# ECU_Sheet2.net
KiCad netlist of a schematic drawn in Altium Designer
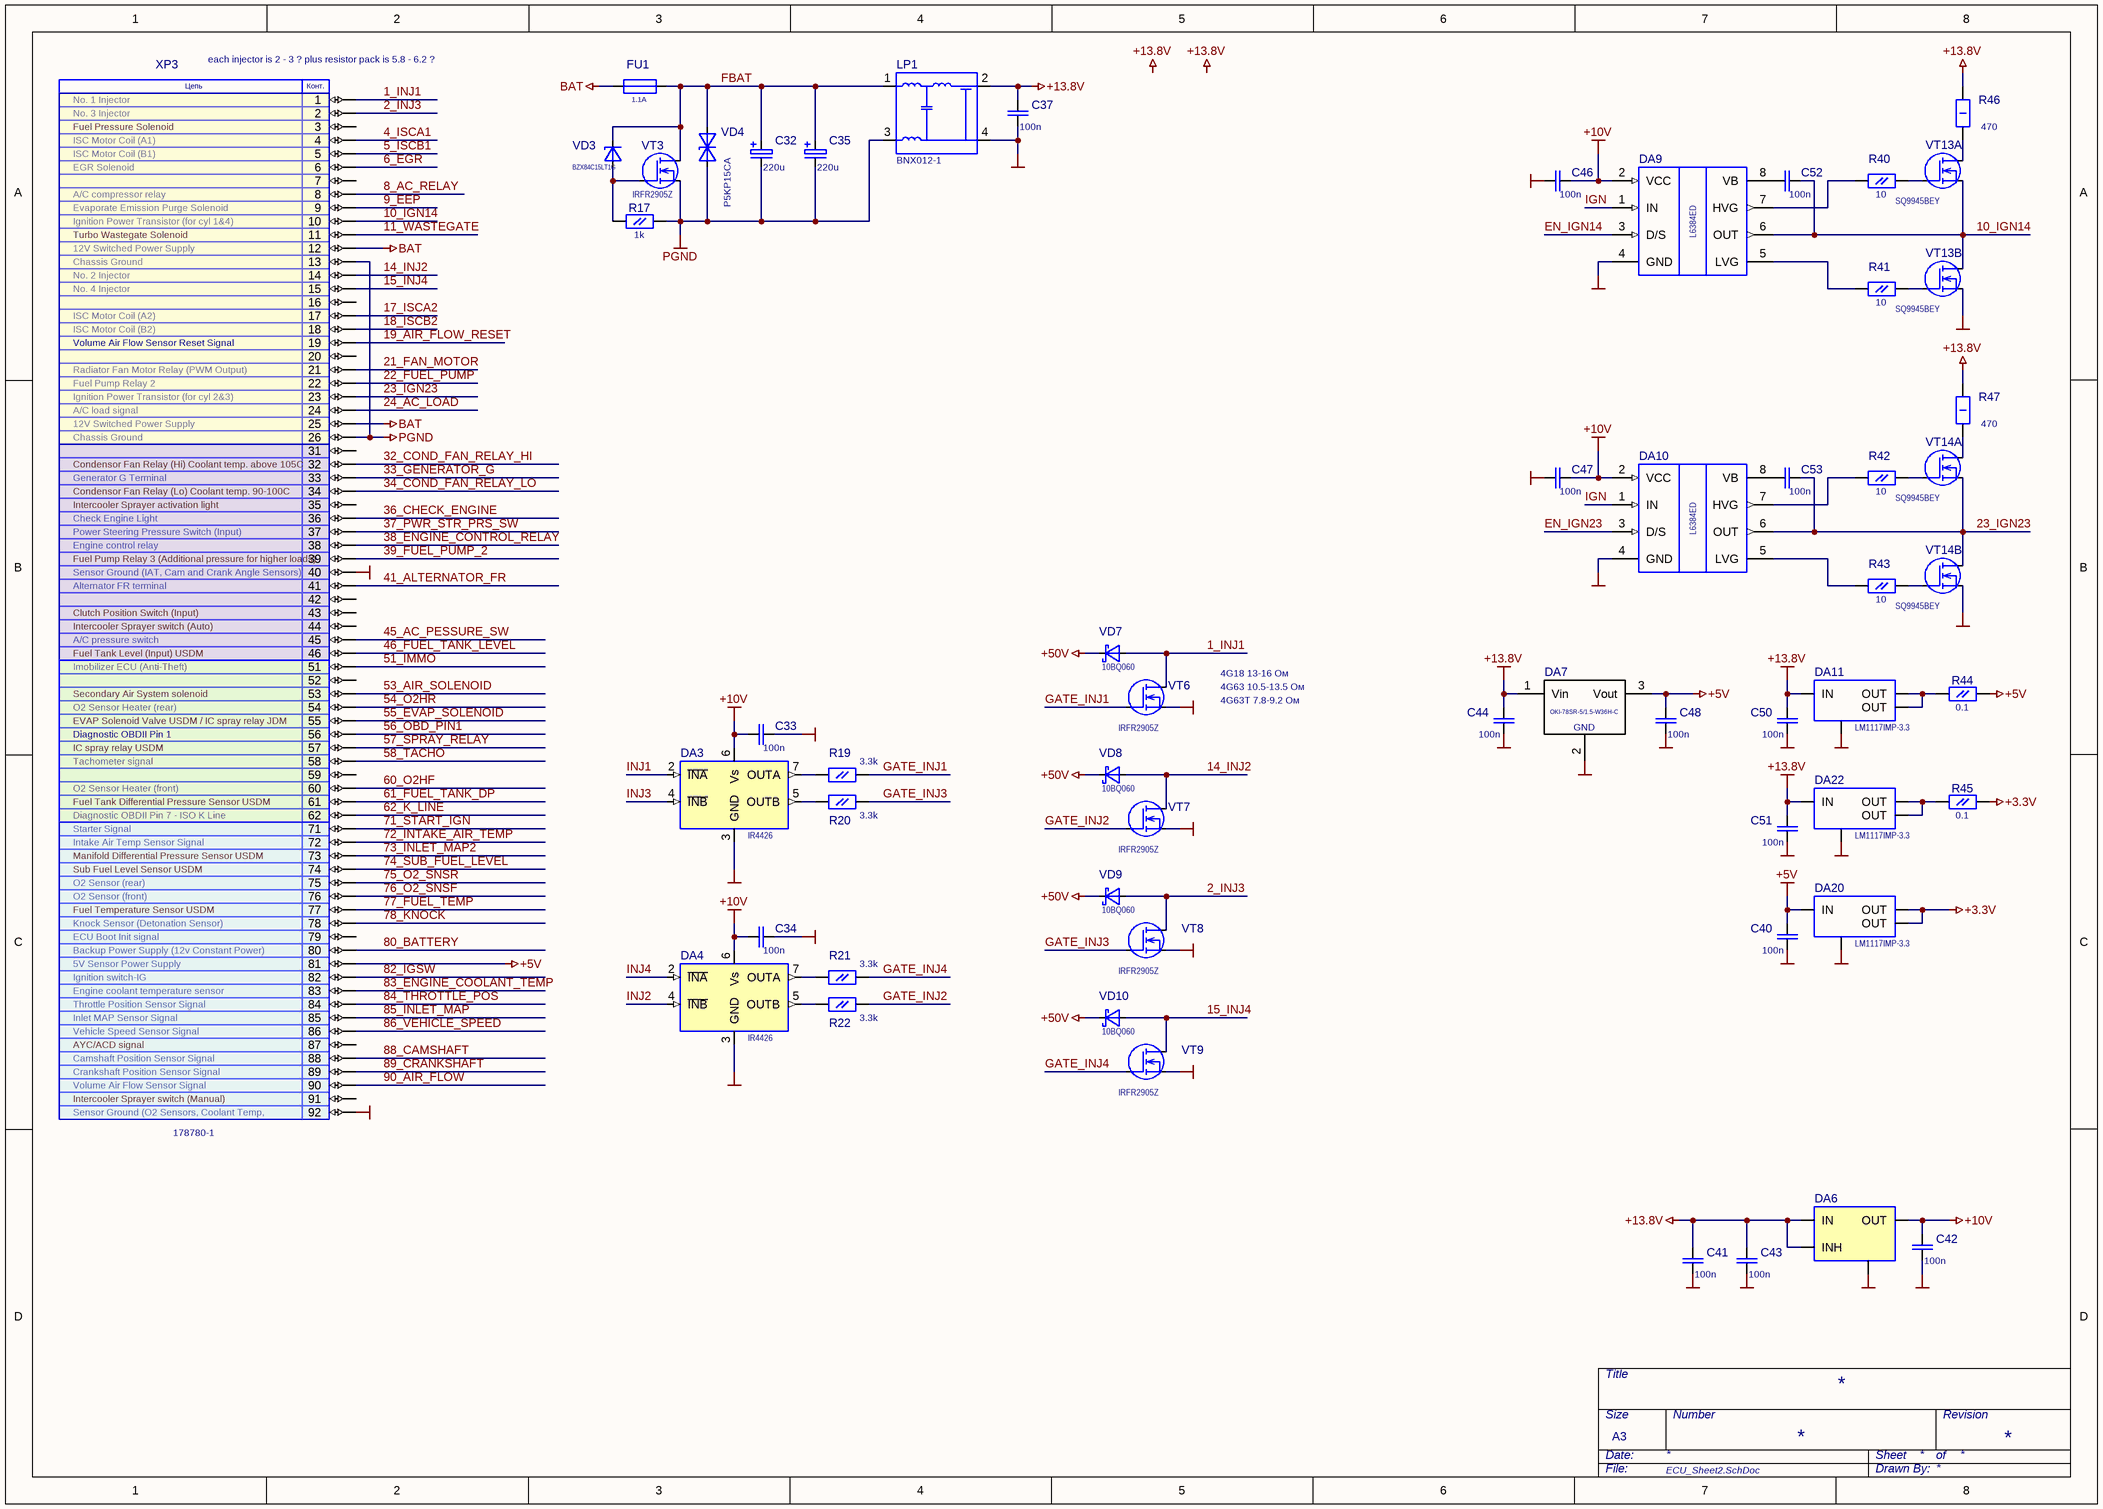
[diagram p0: ECU_Sheet2.SchDoc]

(export (version "E")
  (design (tool "Eeschema 10.0.6"))
  (components
    (comp (ref "C32")
      (value "220u")
      (footprint "C_D_POL")
      (description "220 mkF  25 v (корпус Е (4,4х7мм))  20% smd   Танталовый    ЧИП    227M025V")
      (fields (field (name "Comment") "CTANT"))
      (libsource (lib "L1") (part "CTANT"))
    )
    (comp (ref "C33")
      (value "100n")
      (footprint "C0805L")
      (description "C0603")
      (fields (field (name "Comment") "CSMD"))
      (libsource (lib "L1") (part "CSMD"))
    )
    (comp (ref "C34")
      (value "100n")
      (footprint "C0805L")
      (description "C0603")
      (fields (field (name "Comment") "CSMD"))
      (libsource (lib "L1") (part "CSMD"))
    )
    (comp (ref "C35")
      (value "220u")
      (footprint "C_D_POL")
      (description "220 mkF  25 v (корпус Е (4,4х7мм))  20% smd   Танталовый    ЧИП    227M025V")
      (fields (field (name "Comment") "CTANT"))
      (libsource (lib "L1") (part "CTANT"))
    )
    (comp (ref "C37")
      (value "100n")
      (footprint "C0805L")
      (description "C0603")
      (fields (field (name "Comment") "0.1мкФ-25В-X8R-10%"))
      (libsource (lib "L1") (part "CSMD"))
    )
    (comp (ref "C40")
      (value "100n")
      (footprint "C0805L")
      (description "C0603")
      (fields (field (name "Comment") "CSMD"))
      (libsource (lib "L1") (part "CSMD"))
    )
    (comp (ref "C41")
      (value "100n")
      (footprint "C0805L")
      (description "C0603")
      (fields (field (name "Comment") "0.1мкФ-25В-X8R-10%"))
      (libsource (lib "L1") (part "CSMD"))
    )
    (comp (ref "C42")
      (value "100n")
      (footprint "C0805L")
      (description "C0603")
      (fields (field (name "Comment") "0.1мкФ-25В-X8R-10%"))
      (libsource (lib "L1") (part "CSMD"))
    )
    (comp (ref "C43")
      (value "100n")
      (footprint "C0805L")
      (description "C0603")
      (fields (field (name "Comment") "0.1мкФ-25В-X8R-10%"))
      (libsource (lib "L1") (part "CSMD"))
    )
    (comp (ref "C44")
      (value "100n")
      (footprint "C0805L")
      (description "C0603")
      (fields (field (name "Comment") "CSMD"))
      (libsource (lib "L1") (part "CSMD"))
    )
    (comp (ref "C46")
      (value "100n")
      (footprint "C0805L")
      (description "C0603")
      (fields (field (name "Comment") "CSMD"))
      (libsource (lib "L1") (part "CSMD"))
    )
    (comp (ref "C47")
      (value "100n")
      (footprint "C0805L")
      (description "C0603")
      (fields (field (name "Comment") "CSMD"))
      (libsource (lib "L1") (part "CSMD"))
    )
    (comp (ref "C48")
      (value "100n")
      (footprint "C0805L")
      (description "C0603")
      (fields (field (name "Comment") "CSMD"))
      (libsource (lib "L1") (part "CSMD"))
    )
    (comp (ref "C50")
      (value "100n")
      (footprint "C0805L")
      (description "C0603")
      (fields (field (name "Comment") "CSMD"))
      (libsource (lib "L1") (part "CSMD"))
    )
    (comp (ref "C51")
      (value "100n")
      (footprint "C0805L")
      (description "C0603")
      (fields (field (name "Comment") "CSMD"))
      (libsource (lib "L1") (part "CSMD"))
    )
    (comp (ref "C52")
      (value "100n")
      (footprint "C0805L")
      (description "C0603")
      (fields (field (name "Comment") "CSMD"))
      (libsource (lib "L1") (part "CSMD"))
    )
    (comp (ref "C53")
      (value "100n")
      (footprint "C0805L")
      (description "C0603")
      (fields (field (name "Comment") "CSMD"))
      (libsource (lib "L1") (part "CSMD"))
    )
    (comp (ref "DA3") (value "IR4426") (footprint "SOIC8 JEDEC") (libsource (lib "SCH") (part "IR4426")))
    (comp (ref "DA4") (value "IR4426") (footprint "SOIC8 JEDEC") (libsource (lib "SCH") (part "IR4426")))
    (comp (ref "DA6")
      (value "TLE4266GS V10")
      (footprint "SOT-223")
      (description "TLE4266G")
      (libsource (lib "L1") (part "TLE4266G"))
    )
    (comp (ref "DA7")
      (value "OKI-78SR-5/1.5-W36H-C")
      (footprint "OKI-78SR-H")
      (description "Fixed Output 1.5 Amp SIP DC/DC Converter")
      (libsource (lib "L1") (part "OKI-78SR"))
    )
    (comp (ref "DA9") (value "L6384ED") (footprint "SOIC8 JEDEC") (libsource (lib "ECULIB") (part "L6384ED")))
    (comp (ref "DA10")
      (value "L6384ED")
      (footprint "SOIC8 JEDEC")
      (libsource (lib "ECULIB") (part "L6384ED"))
    )
    (comp (ref "DA11")
      (value "LM1117IMP-3.3")
      (footprint "SOT-223")
      (libsource (lib "RL1") (part "LM1117IMP-3.3"))
    )
    (comp (ref "DA20")
      (value "LM1117IMP-3.3")
      (footprint "SOT-223")
      (libsource (lib "RL1") (part "LM1117IMP-3.3"))
    )
    (comp (ref "DA22")
      (value "LM1117IMP-3.3")
      (footprint "SOT-223")
      (libsource (lib "RL1") (part "LM1117IMP-3.3"))
    )
    (comp (ref "FU1")
      (value "1.1A")
      (footprint "FUSE1206")
      (description "MF-NSMF110")
      (libsource (lib "RL1") (part "MF-NSMF012"))
    )
    (comp (ref "LP1") (value "BNX012-1") (footprint "BNX012-01") (libsource (lib "RL1") (part "BNX012-1")))
    (comp (ref "R17")
      (value "1k")
      (footprint "R0805L")
      (description "R0805")
      (fields (field (name "Comment") "1к-5%"))
      (libsource (lib "L1") (part "RSMD"))
    )
    (comp (ref "R19")
      (value "3.3k")
      (footprint "R0603L")
      (description "R0805")
      (fields (field (name "Comment") "RSMD"))
      (libsource (lib "L1") (part "RSMD"))
    )
    (comp (ref "R20")
      (value "3.3k")
      (footprint "R0603L")
      (description "R0805")
      (fields (field (name "Comment") "RSMD"))
      (libsource (lib "L1") (part "RSMD"))
    )
    (comp (ref "R21")
      (value "3.3k")
      (footprint "R0603L")
      (description "R0805")
      (fields (field (name "Comment") "RSMD"))
      (libsource (lib "L1") (part "RSMD"))
    )
    (comp (ref "R22")
      (value "3.3k")
      (footprint "R0603L")
      (description "R0805")
      (fields (field (name "Comment") "RSMD"))
      (libsource (lib "L1") (part "RSMD"))
    )
    (comp (ref "R40")
      (value "10")
      (footprint "R0603L")
      (description "R0805")
      (fields (field (name "Comment") "RSMD"))
      (libsource (lib "L1") (part "RSMD"))
    )
    (comp (ref "R41")
      (value "10")
      (footprint "R0603L")
      (description "R0805")
      (fields (field (name "Comment") "RSMD"))
      (libsource (lib "L1") (part "RSMD"))
    )
    (comp (ref "R42")
      (value "10")
      (footprint "R0603L")
      (description "R0805")
      (fields (field (name "Comment") "RSMD"))
      (libsource (lib "L1") (part "RSMD"))
    )
    (comp (ref "R43")
      (value "10")
      (footprint "R0603L")
      (description "R0805")
      (fields (field (name "Comment") "RSMD"))
      (libsource (lib "L1") (part "RSMD"))
    )
    (comp (ref "R44")
      (value "0.1")
      (footprint "R0805L")
      (description "R0805")
      (fields (field (name "Comment") "1к-5%"))
      (libsource (lib "L1") (part "RSMD"))
    )
    (comp (ref "R45")
      (value "0.1")
      (footprint "R0805L")
      (description "R0805")
      (fields (field (name "Comment") "1к-5%"))
      (libsource (lib "L1") (part "RSMD"))
    )
    (comp (ref "R46")
      (value "470")
      (footprint "R2512")
      (description "R2512")
      (libsource (lib "RL1") (part "R2512"))
    )
    (comp (ref "R47")
      (value "470")
      (footprint "R2512")
      (description "R2512")
      (libsource (lib "RL1") (part "R2512"))
    )
    (comp (ref "VD3") (value "BZX84C15LT1G") (footprint "SOT-23") (libsource (lib "RL1") (part "BZX84C36")))
    (comp (ref "VD4") (value "P5KP15CA") (footprint "P600") (libsource (lib "L1") (part "P5KP15CA")))
    (comp (ref "VD7")
      (value "10BQ060")
      (footprint "RL1:DO-214AA SMB")
      (libsource (lib "RL1") (part "10BQ060"))
    )
    (comp (ref "VD8")
      (value "10BQ060")
      (footprint "RL1:DO-214AA SMB")
      (libsource (lib "RL1") (part "10BQ060"))
    )
    (comp (ref "VD9")
      (value "10BQ060")
      (footprint "RL1:DO-214AA SMB")
      (libsource (lib "RL1") (part "10BQ060"))
    )
    (comp (ref "VD10")
      (value "10BQ060")
      (footprint "RL1:DO-214AA SMB")
      (libsource (lib "RL1") (part "10BQ060"))
    )
    (comp (ref "VT3")
      (value "IRFR2905Z")
      (footprint "D-PAK (TO-252)")
      (description "MOSFET 55V , 42A , 0.011 Om")
      (libsource (lib "RL1") (part "SPD02N80C3"))
    )
    (comp (ref "VT6")
      (value "IRFR2905Z")
      (footprint "D-PAK (TO-252)")
      (description "MOSFET 55V , 42A , 0.011 Om")
      (libsource (lib "RL1") (part "SPD02N80C3"))
    )
    (comp (ref "VT7")
      (value "IRFR2905Z")
      (footprint "D-PAK (TO-252)")
      (description "MOSFET 55V , 42A , 0.011 Om")
      (libsource (lib "RL1") (part "SPD02N80C3"))
    )
    (comp (ref "VT8")
      (value "IRFR2905Z")
      (footprint "D-PAK (TO-252)")
      (description "MOSFET 55V , 42A , 0.011 Om")
      (libsource (lib "RL1") (part "SPD02N80C3"))
    )
    (comp (ref "VT9")
      (value "IRFR2905Z")
      (footprint "D-PAK (TO-252)")
      (description "MOSFET 55V , 42A , 0.011 Om")
      (libsource (lib "RL1") (part "SPD02N80C3"))
    )
    (comp (ref "VT13")
      (value "SQ9945BEY")
      (footprint "SOIC8 DBL FET")
      (libsource (lib "L1") (part "SQ9945BEY"))
    )
    (comp (ref "VT14")
      (value "SQ9945BEY")
      (footprint "SOIC8 DBL FET")
      (libsource (lib "L1") (part "SQ9945BEY"))
    )
    (comp (ref "XP3")
      (value "178780-1")
      (footprint "MITSUBISHI_ECU_CON")
      (description "TE 178780-1")
      (libsource (lib "ECULIB") (part "MITSUBISHI_ECU_CON"))
    )
  )
  (nets
    (net (code "1") (name "+3.3V") (class "Default")
      (node (ref "DA20") (pin "2") (pinfunction "OUT_2") (pintype "passive"))
      (node (ref "DA20") (pin "4") (pinfunction "OUT_4") (pintype "passive"))
      (node (ref "R45") (pin "1") (pinfunction "Pin1_1") (pintype "passive"))
    )
    (net (code "2") (name "+5V") (class "Default")
      (node (ref "C40") (pin "1") (pintype "passive"))
      (node (ref "C48") (pin "1") (pintype "passive"))
      (node (ref "DA20") (pin "3") (pinfunction "IN_3") (pintype "passive"))
      (node (ref "DA7") (pin "3") (pinfunction "Vout_3") (pintype "passive"))
      (node (ref "R44") (pin "1") (pinfunction "Pin1_1") (pintype "passive"))
      (node (ref "XP3") (pin "81") (pinfunction "81_81") (pintype "bidirectional"))
    )
    (net (code "3") (name "+10V") (class "Default")
      (node (ref "C33") (pin "2") (pintype "passive"))
      (node (ref "C34") (pin "2") (pintype "passive"))
      (node (ref "C42") (pin "1") (pintype "passive"))
      (node (ref "C46") (pin "1") (pintype "passive"))
      (node (ref "C47") (pin "1") (pintype "passive"))
      (node (ref "DA10") (pin "2") (pinfunction "VCC_2") (pintype "input"))
      (node (ref "DA3") (pin "6") (pinfunction "Vs_6") (pintype "power_in"))
      (node (ref "DA4") (pin "6") (pinfunction "Vs_6") (pintype "power_in"))
      (node (ref "DA6") (pin "3") (pinfunction "OUT_3") (pintype "passive"))
      (node (ref "DA9") (pin "2") (pinfunction "VCC_2") (pintype "input"))
    )
    (net (code "4") (name "+13.8V") (class "Default")
      (node (ref "C37") (pin "1") (pintype "passive"))
      (node (ref "C41") (pin "1") (pintype "passive"))
      (node (ref "C43") (pin "1") (pintype "passive"))
      (node (ref "C44") (pin "1") (pintype "passive"))
      (node (ref "C50") (pin "1") (pintype "passive"))
      (node (ref "C51") (pin "1") (pintype "passive"))
      (node (ref "DA11") (pin "3") (pinfunction "IN_3") (pintype "passive"))
      (node (ref "DA22") (pin "3") (pinfunction "IN_3") (pintype "passive"))
      (node (ref "DA6") (pin "1") (pinfunction "IN_1") (pintype "passive"))
      (node (ref "DA6") (pin "2") (pinfunction "INH_2") (pintype "passive"))
      (node (ref "DA7") (pin "1") (pinfunction "Vin_1") (pintype "passive"))
      (node (ref "LP1") (pin "2") (pinfunction "CB_2") (pintype "passive"))
      (node (ref "R46") (pin "2") (pinfunction "Pin2_2") (pintype "passive"))
      (node (ref "R47") (pin "2") (pinfunction "Pin2_2") (pintype "passive"))
    )
    (net (code "5") (name "+50V") (class "Default")
      (node (ref "VD10") (pin "2") (pintype "passive"))
      (node (ref "VD7") (pin "2") (pintype "passive"))
      (node (ref "VD8") (pin "2") (pintype "passive"))
      (node (ref "VD9") (pin "2") (pintype "passive"))
    )
    (net (code "6") (name "/1_INJ1") (class "Default")
      (node (ref "VD7") (pin "1") (pintype "passive"))
      (node (ref "VT6") (pin "3") (pinfunction "D_3") (pintype "passive"))
      (node (ref "XP3") (pin "1") (pinfunction "1_1") (pintype "bidirectional"))
    )
    (net (code "7") (name "/2_INJ3") (class "Default")
      (node (ref "VD9") (pin "1") (pintype "passive"))
      (node (ref "VT8") (pin "3") (pinfunction "D_3") (pintype "passive"))
      (node (ref "XP3") (pin "2") (pinfunction "2_2") (pintype "bidirectional"))
    )
    (net (code "8") (name "/4_ISCA1") (class "Default")
      (node (ref "XP3") (pin "4") (pinfunction "4_4") (pintype "bidirectional"))
    )
    (net (code "9") (name "/5_ISCB1") (class "Default")
      (node (ref "XP3") (pin "5") (pinfunction "5_5") (pintype "bidirectional"))
    )
    (net (code "10") (name "/6_EGR") (class "Default")
      (node (ref "XP3") (pin "6") (pinfunction "6_6") (pintype "bidirectional"))
    )
    (net (code "11") (name "/8_AC_RELAY") (class "Default")
      (node (ref "XP3") (pin "8") (pinfunction "8_8") (pintype "bidirectional"))
    )
    (net (code "12") (name "/9_EEP") (class "Default")
      (node (ref "XP3") (pin "9") (pinfunction "9_9") (pintype "bidirectional"))
    )
    (net (code "13") (name "/10_IGN14") (class "Default")
      (node (ref "C52") (pin "1") (pintype "passive"))
      (node (ref "DA9") (pin "6") (pinfunction "OUT_6") (pintype "output"))
      (node (ref "VT13") (pin "1") (pintype "passive"))
      (node (ref "VT13") (pin "5") (pintype "passive"))
      (node (ref "XP3") (pin "10") (pinfunction "10_10") (pintype "bidirectional"))
    )
    (net (code "14") (name "/11_WASTEGATE") (class "Default")
      (node (ref "XP3") (pin "11") (pinfunction "11_11") (pintype "bidirectional"))
    )
    (net (code "15") (name "/14_INJ2") (class "Default")
      (node (ref "VD8") (pin "1") (pintype "passive"))
      (node (ref "VT7") (pin "3") (pinfunction "D_3") (pintype "passive"))
      (node (ref "XP3") (pin "14") (pinfunction "14_14") (pintype "bidirectional"))
    )
    (net (code "16") (name "/15_INJ4") (class "Default")
      (node (ref "VD10") (pin "1") (pintype "passive"))
      (node (ref "VT9") (pin "3") (pinfunction "D_3") (pintype "passive"))
      (node (ref "XP3") (pin "15") (pinfunction "15_15") (pintype "bidirectional"))
    )
    (net (code "17") (name "/17_ISCA2") (class "Default")
      (node (ref "XP3") (pin "17") (pinfunction "17_17") (pintype "bidirectional"))
    )
    (net (code "18") (name "/18_ISCB2") (class "Default")
      (node (ref "XP3") (pin "18") (pinfunction "18_18") (pintype "bidirectional"))
    )
    (net (code "19") (name "/19_AIR_FLOW_RESET") (class "Default")
      (node (ref "XP3") (pin "19") (pinfunction "19_19") (pintype "bidirectional"))
    )
    (net (code "20") (name "/21_FAN_MOTOR") (class "Default")
      (node (ref "XP3") (pin "21") (pinfunction "21_21") (pintype "bidirectional"))
    )
    (net (code "21") (name "/22_FUEL_PUMP") (class "Default")
      (node (ref "XP3") (pin "22") (pinfunction "22_22") (pintype "bidirectional"))
    )
    (net (code "22") (name "/23_IGN23") (class "Default")
      (node (ref "C53") (pin "1") (pintype "passive"))
      (node (ref "DA10") (pin "6") (pinfunction "OUT_6") (pintype "output"))
      (node (ref "VT14") (pin "1") (pintype "passive"))
      (node (ref "VT14") (pin "5") (pintype "passive"))
      (node (ref "XP3") (pin "23") (pinfunction "23_23") (pintype "bidirectional"))
    )
    (net (code "23") (name "/24_AC_LOAD") (class "Default")
      (node (ref "XP3") (pin "24") (pinfunction "24_24") (pintype "bidirectional"))
    )
    (net (code "24") (name "/32_COND_FAN_RELAY_HI") (class "Default")
      (node (ref "XP3") (pin "32") (pinfunction "32_32") (pintype "bidirectional"))
    )
    (net (code "25") (name "/33_GENERATOR_G") (class "Default")
      (node (ref "XP3") (pin "33") (pinfunction "33_33") (pintype "bidirectional"))
    )
    (net (code "26") (name "/34_COND_FAN_RELAY_LO") (class "Default")
      (node (ref "XP3") (pin "34") (pinfunction "34_34") (pintype "bidirectional"))
    )
    (net (code "27") (name "/36_CHECK_ENGINE") (class "Default")
      (node (ref "XP3") (pin "36") (pinfunction "36_36") (pintype "bidirectional"))
    )
    (net (code "28") (name "/37_PWR_STR_PRS_SW") (class "Default")
      (node (ref "XP3") (pin "37") (pinfunction "37_37") (pintype "bidirectional"))
    )
    (net (code "29") (name "/38_ENGINE_CONTROL_RELAY") (class "Default")
      (node (ref "XP3") (pin "38") (pinfunction "38_38") (pintype "bidirectional"))
    )
    (net (code "30") (name "/39_FUEL_PUMP_2") (class "Default")
      (node (ref "XP3") (pin "39") (pinfunction "39_39") (pintype "bidirectional"))
    )
    (net (code "31") (name "/41_ALTERNATOR_FR") (class "Default")
      (node (ref "XP3") (pin "41") (pinfunction "41_41") (pintype "bidirectional"))
    )
    (net (code "32") (name "/45_AC_PESSURE_SW") (class "Default")
      (node (ref "XP3") (pin "45") (pinfunction "45_45") (pintype "bidirectional"))
    )
    (net (code "33") (name "/46_FUEL_TANK_LEVEL") (class "Default")
      (node (ref "XP3") (pin "46") (pinfunction "46_46") (pintype "bidirectional"))
    )
    (net (code "34") (name "/51_IMMO") (class "Default")
      (node (ref "XP3") (pin "51") (pinfunction "51_51") (pintype "bidirectional"))
    )
    (net (code "35") (name "/53_AIR_SOLENOID") (class "Default")
      (node (ref "XP3") (pin "53") (pinfunction "53_53") (pintype "bidirectional"))
    )
    (net (code "36") (name "/54_O2HR") (class "Default")
      (node (ref "XP3") (pin "54") (pinfunction "54_54") (pintype "bidirectional"))
    )
    (net (code "37") (name "/55_EVAP_SOLENOID") (class "Default")
      (node (ref "XP3") (pin "55") (pinfunction "55_55") (pintype "bidirectional"))
    )
    (net (code "38") (name "/56_OBD_PIN1") (class "Default")
      (node (ref "XP3") (pin "56") (pinfunction "56_56") (pintype "bidirectional"))
    )
    (net (code "39") (name "/57_SPRAY_RELAY") (class "Default")
      (node (ref "XP3") (pin "57") (pinfunction "57_57") (pintype "bidirectional"))
    )
    (net (code "40") (name "/58_TACHO") (class "Default")
      (node (ref "XP3") (pin "58") (pinfunction "58_58") (pintype "bidirectional"))
    )
    (net (code "41") (name "/60_O2HF") (class "Default")
      (node (ref "XP3") (pin "60") (pinfunction "60_60") (pintype "bidirectional"))
    )
    (net (code "42") (name "/61_FUEL_TANK_DP") (class "Default")
      (node (ref "XP3") (pin "61") (pinfunction "61_61") (pintype "bidirectional"))
    )
    (net (code "43") (name "/62_K_LINE") (class "Default")
      (node (ref "XP3") (pin "62") (pinfunction "62_62") (pintype "bidirectional"))
    )
    (net (code "44") (name "/71_START_IGN") (class "Default")
      (node (ref "XP3") (pin "71") (pinfunction "71_71") (pintype "bidirectional"))
    )
    (net (code "45") (name "/72_INTAKE_AIR_TEMP") (class "Default")
      (node (ref "XP3") (pin "72") (pinfunction "72_72") (pintype "bidirectional"))
    )
    (net (code "46") (name "/73_INLET_MAP2") (class "Default")
      (node (ref "XP3") (pin "73") (pinfunction "73_73") (pintype "bidirectional"))
    )
    (net (code "47") (name "/74_SUB_FUEL_LEVEL") (class "Default")
      (node (ref "XP3") (pin "74") (pinfunction "74_74") (pintype "bidirectional"))
    )
    (net (code "48") (name "/75_O2_SNSR") (class "Default")
      (node (ref "XP3") (pin "75") (pinfunction "75_75") (pintype "bidirectional"))
    )
    (net (code "49") (name "/76_O2_SNSF") (class "Default")
      (node (ref "XP3") (pin "76") (pinfunction "76_76") (pintype "bidirectional"))
    )
    (net (code "50") (name "/77_FUEL_TEMP") (class "Default")
      (node (ref "XP3") (pin "77") (pinfunction "77_77") (pintype "bidirectional"))
    )
    (net (code "51") (name "/78_KNOCK") (class "Default")
      (node (ref "XP3") (pin "78") (pinfunction "78_78") (pintype "bidirectional"))
    )
    (net (code "52") (name "/80_BATTERY") (class "Default")
      (node (ref "XP3") (pin "80") (pinfunction "80_80") (pintype "bidirectional"))
    )
    (net (code "53") (name "/82_IGSW") (class "Default")
      (node (ref "XP3") (pin "82") (pinfunction "82_82") (pintype "bidirectional"))
    )
    (net (code "54") (name "/83_ENGINE_COOLANT_TEMP") (class "Default")
      (node (ref "XP3") (pin "83") (pinfunction "83_83") (pintype "bidirectional"))
    )
    (net (code "55") (name "/84_THROTTLE_POS") (class "Default")
      (node (ref "XP3") (pin "84") (pinfunction "84_84") (pintype "bidirectional"))
    )
    (net (code "56") (name "/85_INLET_MAP") (class "Default")
      (node (ref "XP3") (pin "85") (pinfunction "85_85") (pintype "bidirectional"))
    )
    (net (code "57") (name "/86_VEHICLE_SPEED") (class "Default")
      (node (ref "XP3") (pin "86") (pinfunction "86_86") (pintype "bidirectional"))
    )
    (net (code "58") (name "/88_CAMSHAFT") (class "Default")
      (node (ref "XP3") (pin "88") (pinfunction "88_88") (pintype "bidirectional"))
    )
    (net (code "59") (name "/89_CRANKSHAFT") (class "Default")
      (node (ref "XP3") (pin "89") (pinfunction "89_89") (pintype "bidirectional"))
    )
    (net (code "60") (name "/90_AIR_FLOW") (class "Default")
      (node (ref "XP3") (pin "90") (pinfunction "90_90") (pintype "bidirectional"))
    )
    (net (code "61") (name "/EN_IGN14") (class "Default")
      (node (ref "DA9") (pin "3") (pinfunction "D/S_3") (pintype "input"))
    )
    (net (code "62") (name "/EN_IGN23") (class "Default")
      (node (ref "DA10") (pin "3") (pinfunction "D/S_3") (pintype "input"))
    )
    (net (code "63") (name "/FBAT") (class "Default")
      (node (ref "C32") (pin "P") (pintype "passive"))
      (node (ref "C35") (pin "P") (pintype "passive"))
      (node (ref "FU1") (pin "2") (pinfunction "2_2") (pintype "passive"))
      (node (ref "LP1") (pin "1") (pinfunction "B_1") (pintype "passive"))
      (node (ref "VD3") (pin "3") (pintype "passive"))
      (node (ref "VD4") (pin "2") (pintype "passive"))
      (node (ref "VT3") (pin "3") (pinfunction "D_3") (pintype "passive"))
    )
    (net (code "64") (name "/GATE_INJ1") (class "Default")
      (node (ref "R19") (pin "2") (pinfunction "Pin2_2") (pintype "passive"))
      (node (ref "VT6") (pin "1") (pinfunction "G_1") (pintype "passive"))
    )
    (net (code "65") (name "/GATE_INJ2") (class "Default")
      (node (ref "R22") (pin "2") (pinfunction "Pin2_2") (pintype "passive"))
      (node (ref "VT7") (pin "1") (pinfunction "G_1") (pintype "passive"))
    )
    (net (code "66") (name "/GATE_INJ3") (class "Default")
      (node (ref "R20") (pin "2") (pinfunction "Pin2_2") (pintype "passive"))
      (node (ref "VT8") (pin "1") (pinfunction "G_1") (pintype "passive"))
    )
    (net (code "67") (name "/GATE_INJ4") (class "Default")
      (node (ref "R21") (pin "2") (pinfunction "Pin2_2") (pintype "passive"))
      (node (ref "VT9") (pin "1") (pinfunction "G_1") (pintype "passive"))
    )
    (net (code "68") (name "/IGN") (class "Default")
      (node (ref "DA10") (pin "1") (pinfunction "IN_1") (pintype "input"))
      (node (ref "DA9") (pin "1") (pinfunction "IN_1") (pintype "input"))
    )
    (net (code "69") (name "/INJ1") (class "Default")
      (node (ref "DA3") (pin "2") (pinfunction "~{INA}_2") (pintype "input"))
    )
    (net (code "70") (name "/INJ2") (class "Default")
      (node (ref "DA4") (pin "4") (pinfunction "~{INB}_4") (pintype "input"))
    )
    (net (code "71") (name "/INJ3") (class "Default")
      (node (ref "DA3") (pin "4") (pinfunction "~{INB}_4") (pintype "input"))
    )
    (net (code "72") (name "/INJ4") (class "Default")
      (node (ref "DA4") (pin "2") (pinfunction "~{INA}_2") (pintype "input"))
    )
    (net (code "73") (name "BAT") (class "Default")
      (node (ref "FU1") (pin "1") (pinfunction "1_1") (pintype "passive"))
      (node (ref "XP3") (pin "12") (pinfunction "12_12") (pintype "bidirectional"))
      (node (ref "XP3") (pin "25") (pinfunction "25_25") (pintype "bidirectional"))
    )
    (net (code "74") (name "GND") (class "Default")
      (node (ref "C33") (pin "1") (pintype "passive"))
      (node (ref "C34") (pin "1") (pintype "passive"))
      (node (ref "C37") (pin "2") (pintype "passive"))
      (node (ref "C40") (pin "2") (pintype "passive"))
      (node (ref "C41") (pin "2") (pintype "passive"))
      (node (ref "C42") (pin "2") (pintype "passive"))
      (node (ref "C43") (pin "2") (pintype "passive"))
      (node (ref "C44") (pin "2") (pintype "passive"))
      (node (ref "C46") (pin "2") (pintype "passive"))
      (node (ref "C47") (pin "2") (pintype "passive"))
      (node (ref "C48") (pin "2") (pintype "passive"))
      (node (ref "C50") (pin "2") (pintype "passive"))
      (node (ref "C51") (pin "2") (pintype "passive"))
      (node (ref "DA10") (pin "4") (pinfunction "GND_4") (pintype "power_in"))
      (node (ref "DA11") (pin "1") (pinfunction "G_1") (pintype "passive"))
      (node (ref "DA20") (pin "1") (pinfunction "G_1") (pintype "passive"))
      (node (ref "DA22") (pin "1") (pinfunction "G_1") (pintype "passive"))
      (node (ref "DA3") (pin "3") (pinfunction "GND_3") (pintype "power_in"))
      (node (ref "DA4") (pin "3") (pinfunction "GND_3") (pintype "power_in"))
      (node (ref "DA6") (pin "4") (pinfunction "GND_4") (pintype "passive"))
      (node (ref "DA7") (pin "2") (pintype "passive"))
      (node (ref "DA9") (pin "4") (pinfunction "GND_4") (pintype "power_in"))
      (node (ref "LP1") (pin "4") (pinfunction "CG_4") (pintype "passive"))
      (node (ref "VT13") (pin "3") (pintype "passive"))
      (node (ref "VT14") (pin "3") (pintype "passive"))
      (node (ref "VT6") (pin "2") (pinfunction "S_2") (pintype "passive"))
      (node (ref "VT7") (pin "2") (pinfunction "S_2") (pintype "passive"))
      (node (ref "VT8") (pin "2") (pinfunction "S_2") (pintype "passive"))
      (node (ref "VT9") (pin "2") (pinfunction "S_2") (pintype "passive"))
      (node (ref "XP3") (pin "40") (pinfunction "40_40") (pintype "bidirectional"))
      (node (ref "XP3") (pin "92") (pinfunction "92_92") (pintype "bidirectional"))
    )
    (net (code "75") (name "Net-(DA3-OUTA)") (class "Default")
      (node (ref "DA3") (pin "7") (pinfunction "OUTA_7") (pintype "output"))
      (node (ref "R19") (pin "1") (pinfunction "Pin1_1") (pintype "passive"))
    )
    (net (code "76") (name "Net-(DA3-OUTB)") (class "Default")
      (node (ref "DA3") (pin "5") (pinfunction "OUTB_5") (pintype "output"))
      (node (ref "R20") (pin "1") (pinfunction "Pin1_1") (pintype "passive"))
    )
    (net (code "77") (name "Net-(DA4-OUTA)") (class "Default")
      (node (ref "DA4") (pin "7") (pinfunction "OUTA_7") (pintype "output"))
      (node (ref "R21") (pin "1") (pinfunction "Pin1_1") (pintype "passive"))
    )
    (net (code "78") (name "Net-(DA4-OUTB)") (class "Default")
      (node (ref "DA4") (pin "5") (pinfunction "OUTB_5") (pintype "output"))
      (node (ref "R22") (pin "1") (pinfunction "Pin1_1") (pintype "passive"))
    )
    (net (code "79") (name "Net-(DA9-HVG)") (class "Default")
      (node (ref "DA9") (pin "7") (pinfunction "HVG_7") (pintype "output"))
      (node (ref "R40") (pin "1") (pinfunction "Pin1_1") (pintype "passive"))
    )
    (net (code "80") (name "Net-(DA9-LVG)") (class "Default")
      (node (ref "DA9") (pin "5") (pinfunction "LVG_5") (pintype "power_in"))
      (node (ref "R41") (pin "1") (pinfunction "Pin1_1") (pintype "passive"))
    )
    (net (code "81") (name "Net-(DA9-VB)") (class "Default")
      (node (ref "C52") (pin "2") (pintype "passive"))
      (node (ref "DA9") (pin "8") (pinfunction "VB_8") (pintype "power_in"))
    )
    (net (code "82") (name "Net-(DA10-HVG)") (class "Default")
      (node (ref "DA10") (pin "7") (pinfunction "HVG_7") (pintype "output"))
      (node (ref "R42") (pin "1") (pinfunction "Pin1_1") (pintype "passive"))
    )
    (net (code "83") (name "Net-(DA10-LVG)") (class "Default")
      (node (ref "DA10") (pin "5") (pinfunction "LVG_5") (pintype "power_in"))
      (node (ref "R43") (pin "1") (pinfunction "Pin1_1") (pintype "passive"))
    )
    (net (code "84") (name "Net-(DA10-VB)") (class "Default")
      (node (ref "C53") (pin "2") (pintype "passive"))
      (node (ref "DA10") (pin "8") (pinfunction "VB_8") (pintype "power_in"))
    )
    (net (code "85") (name "Net-(R17-Pin2)") (class "Default")
      (node (ref "R17") (pin "2") (pinfunction "Pin2_2") (pintype "passive"))
      (node (ref "VD3") (pin "1") (pintype "passive"))
      (node (ref "VT3") (pin "1") (pinfunction "G_1") (pintype "passive"))
    )
    (net (code "86") (name "Net-(R40-Pin2)") (class "Default")
      (node (ref "R40") (pin "2") (pinfunction "Pin2_2") (pintype "passive"))
      (node (ref "VT13") (pin "2") (pintype "passive"))
    )
    (net (code "87") (name "Net-(R41-Pin2)") (class "Default")
      (node (ref "R41") (pin "2") (pinfunction "Pin2_2") (pintype "passive"))
      (node (ref "VT13") (pin "4") (pintype "passive"))
    )
    (net (code "88") (name "Net-(R42-Pin2)") (class "Default")
      (node (ref "R42") (pin "2") (pinfunction "Pin2_2") (pintype "passive"))
      (node (ref "VT14") (pin "2") (pintype "passive"))
    )
    (net (code "89") (name "Net-(R43-Pin2)") (class "Default")
      (node (ref "R43") (pin "2") (pinfunction "Pin2_2") (pintype "passive"))
      (node (ref "VT14") (pin "4") (pintype "passive"))
    )
    (net (code "90") (name "Net-(R44-Pin2)") (class "Default")
      (node (ref "DA11") (pin "2") (pinfunction "OUT_2") (pintype "passive"))
      (node (ref "DA11") (pin "4") (pinfunction "OUT_4") (pintype "passive"))
      (node (ref "R44") (pin "2") (pinfunction "Pin2_2") (pintype "passive"))
    )
    (net (code "91") (name "Net-(R45-Pin2)") (class "Default")
      (node (ref "DA22") (pin "2") (pinfunction "OUT_2") (pintype "passive"))
      (node (ref "DA22") (pin "4") (pinfunction "OUT_4") (pintype "passive"))
      (node (ref "R45") (pin "2") (pinfunction "Pin2_2") (pintype "passive"))
    )
    (net (code "92") (name "Net-(R46-Pin1)") (class "Default")
      (node (ref "R46") (pin "1") (pinfunction "Pin1_1") (pintype "passive"))
      (node (ref "VT13") (pin "6") (pintype "passive"))
    )
    (net (code "93") (name "Net-(R47-Pin1)") (class "Default")
      (node (ref "R47") (pin "1") (pinfunction "Pin1_1") (pintype "passive"))
      (node (ref "VT14") (pin "6") (pintype "passive"))
    )
    (net (code "94") (name "PGND") (class "Default")
      (node (ref "C32") (pin "N") (pintype "passive"))
      (node (ref "C35") (pin "N") (pintype "passive"))
      (node (ref "LP1") (pin "3") (pinfunction "PSG_3") (pintype "passive"))
      (node (ref "R17") (pin "1") (pinfunction "Pin1_1") (pintype "passive"))
      (node (ref "VD4") (pin "1") (pintype "passive"))
      (node (ref "VT3") (pin "2") (pinfunction "S_2") (pintype "passive"))
      (node (ref "XP3") (pin "13") (pinfunction "13_13") (pintype "bidirectional"))
      (node (ref "XP3") (pin "26") (pinfunction "26_26") (pintype "bidirectional"))
    )
    (net (code "95") (name "unconnected-(LP1-Pad5)") (class "Default")
      (node (ref "LP1") (pin "5") (pintype "passive"))
    )
    (net (code "96") (name "unconnected-(LP1-Pad6)") (class "Default")
      (node (ref "LP1") (pin "6") (pintype "passive"))
    )
    (net (code "97") (name "unconnected-(XP3-Pad3)") (class "Default")
      (node (ref "XP3") (pin "3") (pinfunction "3_3") (pintype "bidirectional"))
    )
    (net (code "98") (name "unconnected-(XP3-Pad7)") (class "Default")
      (node (ref "XP3") (pin "7") (pinfunction "7_7") (pintype "bidirectional"))
    )
    (net (code "99") (name "unconnected-(XP3-Pad16)") (class "Default")
      (node (ref "XP3") (pin "16") (pinfunction "16_16") (pintype "bidirectional"))
    )
    (net (code "100") (name "unconnected-(XP3-Pad20)") (class "Default")
      (node (ref "XP3") (pin "20") (pinfunction "20_20") (pintype "bidirectional"))
    )
    (net (code "101") (name "unconnected-(XP3-Pad31)") (class "Default")
      (node (ref "XP3") (pin "31") (pinfunction "31_31") (pintype "bidirectional"))
    )
    (net (code "102") (name "unconnected-(XP3-Pad35)") (class "Default")
      (node (ref "XP3") (pin "35") (pinfunction "35_35") (pintype "bidirectional"))
    )
    (net (code "103") (name "unconnected-(XP3-Pad42)") (class "Default")
      (node (ref "XP3") (pin "42") (pinfunction "42_42") (pintype "bidirectional"))
    )
    (net (code "104") (name "unconnected-(XP3-Pad43)") (class "Default")
      (node (ref "XP3") (pin "43") (pinfunction "43_43") (pintype "bidirectional"))
    )
    (net (code "105") (name "unconnected-(XP3-Pad44)") (class "Default")
      (node (ref "XP3") (pin "44") (pinfunction "44_44") (pintype "bidirectional"))
    )
    (net (code "106") (name "unconnected-(XP3-Pad52)") (class "Default")
      (node (ref "XP3") (pin "52") (pinfunction "52_52") (pintype "bidirectional"))
    )
    (net (code "107") (name "unconnected-(XP3-Pad59)") (class "Default")
      (node (ref "XP3") (pin "59") (pinfunction "59_59") (pintype "bidirectional"))
    )
    (net (code "108") (name "unconnected-(XP3-Pad79)") (class "Default")
      (node (ref "XP3") (pin "79") (pinfunction "79_79") (pintype "bidirectional"))
    )
    (net (code "109") (name "unconnected-(XP3-Pad87)") (class "Default")
      (node (ref "XP3") (pin "87") (pinfunction "87_87") (pintype "bidirectional"))
    )
    (net (code "110") (name "unconnected-(XP3-Pad91)") (class "Default")
      (node (ref "XP3") (pin "91") (pinfunction "91_91") (pintype "bidirectional"))
    )
  )
)
